# ST-LINK-SCH.net
KiCad netlist of a schematic drawn in Altium Designer
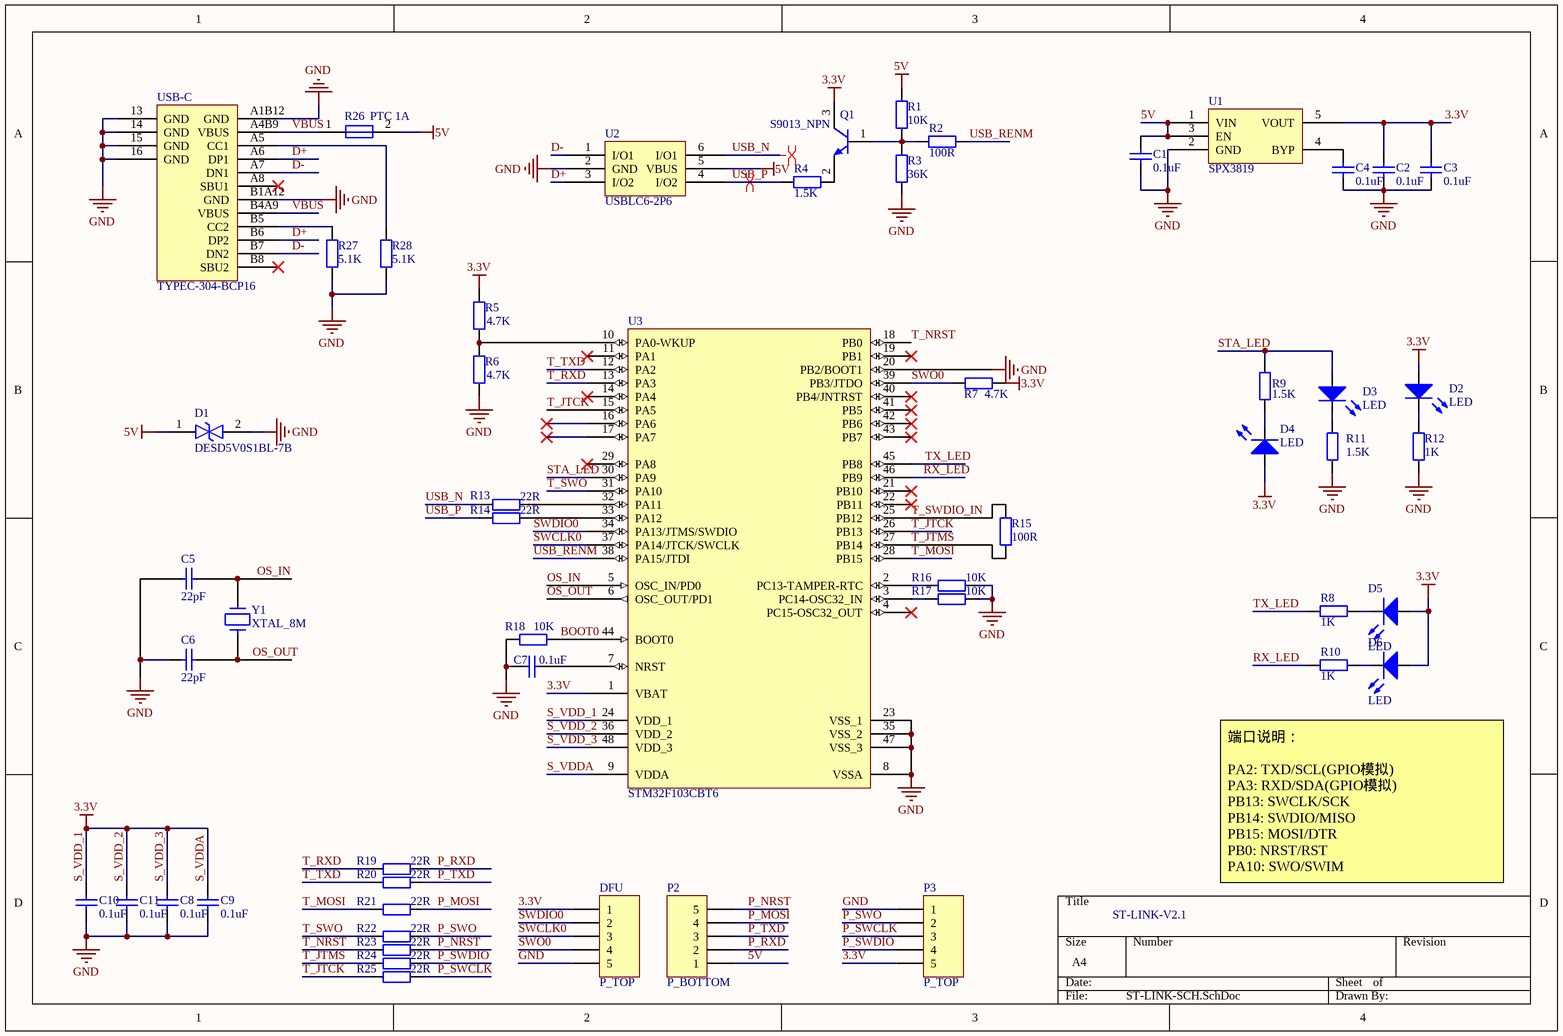
[diagram p0: ST-LINK-SCH.SchDoc]

(export (version "E")
  (design (tool "Eeschema 10.0.6"))
  (components
    (comp (ref "C1")
      (value "0.1uF")
      (footprint "0402C")
      (description "Capacitor")
      (fields (field (name "Comment") "Cap") (field (name "PUBLISHER") "Altium Limited"))
      (libsource (lib "ST-LINK-SCHLIB") (part "Cap"))
    )
    (comp (ref "C2")
      (value "0.1uF")
      (footprint "0402C")
      (description "Capacitor")
      (fields (field (name "Comment") "Cap") (field (name "PUBLISHER") "Altium Limited"))
      (libsource (lib "ST-LINK-SCHLIB") (part "Cap"))
    )
    (comp (ref "C3")
      (value "0.1uF")
      (footprint "0402C")
      (description "Capacitor")
      (fields (field (name "Comment") "Cap") (field (name "PUBLISHER") "Altium Limited"))
      (libsource (lib "ST-LINK-SCHLIB") (part "Cap"))
    )
    (comp (ref "C4")
      (value "0.1uF")
      (footprint "0402C")
      (description "Capacitor")
      (fields (field (name "Comment") "Cap") (field (name "PUBLISHER") "Altium Limited"))
      (libsource (lib "ST-LINK-SCHLIB") (part "Cap"))
    )
    (comp (ref "C5")
      (value "22pF")
      (footprint "0402C")
      (description "Capacitor")
      (fields (field (name "Comment") "Cap") (field (name "PUBLISHER") "Altium Limited"))
      (libsource (lib "ST-LINK-SCHLIB") (part "Cap"))
    )
    (comp (ref "C6")
      (value "22pF")
      (footprint "0402C")
      (description "Capacitor")
      (fields (field (name "Comment") "Cap") (field (name "PUBLISHER") "Altium Limited"))
      (libsource (lib "ST-LINK-SCHLIB") (part "Cap"))
    )
    (comp (ref "C7")
      (value "0.1uF")
      (footprint "0402C")
      (description "Capacitor")
      (fields (field (name "Comment") "Cap") (field (name "PUBLISHER") "Altium Limited"))
      (libsource (lib "ST-LINK-SCHLIB") (part "Cap"))
    )
    (comp (ref "C8")
      (value "0.1uF")
      (footprint "0402C")
      (description "Capacitor")
      (fields (field (name "Comment") "Cap") (field (name "PUBLISHER") "Altium Limited"))
      (libsource (lib "ST-LINK-SCHLIB") (part "Cap"))
    )
    (comp (ref "C9")
      (value "0.1uF")
      (footprint "0402C")
      (description "Capacitor")
      (fields (field (name "Comment") "Cap") (field (name "PUBLISHER") "Altium Limited"))
      (libsource (lib "ST-LINK-SCHLIB") (part "Cap"))
    )
    (comp (ref "C10")
      (value "0.1uF")
      (footprint "0402C")
      (description "Capacitor")
      (fields (field (name "Comment") "Cap") (field (name "PUBLISHER") "Altium Limited"))
      (libsource (lib "ST-LINK-SCHLIB") (part "Cap"))
    )
    (comp (ref "C11")
      (value "0.1uF")
      (footprint "0402C")
      (description "Capacitor")
      (fields (field (name "Comment") "Cap") (field (name "PUBLISHER") "Altium Limited"))
      (libsource (lib "ST-LINK-SCHLIB") (part "Cap"))
    )
    (comp (ref "D1")
      (value "DESD5V0S1BL-7B")
      (footprint "DESD5V0S1BL-7B")
      (description "1CHANNEL ESD")
      (libsource (lib "ST-LINK-SCHLIB") (part "DESD5V0S1BL-7B"))
    )
    (comp (ref "D2")
      (value "LED")
      (footprint "0603LED")
      (description "Typical RED, GREEN, YELLOW, AMBER GaAs LED")
      (fields (field (name "PUBLISHER") "Altium Limited"))
      (libsource (lib "ST-LINK-SCHLIB") (part "LED"))
    )
    (comp (ref "D3")
      (value "LED")
      (footprint "0603LED")
      (description "Typical RED, GREEN, YELLOW, AMBER GaAs LED")
      (fields (field (name "PUBLISHER") "Altium Limited"))
      (libsource (lib "ST-LINK-SCHLIB") (part "LED"))
    )
    (comp (ref "D4")
      (value "LED")
      (footprint "0603LED")
      (description "Typical RED, GREEN, YELLOW, AMBER GaAs LED")
      (fields (field (name "PUBLISHER") "Altium Limited"))
      (libsource (lib "ST-LINK-SCHLIB") (part "LED"))
    )
    (comp (ref "D5")
      (value "LED")
      (footprint "0603LED")
      (description "Typical RED, GREEN, YELLOW, AMBER GaAs LED")
      (fields (field (name "PUBLISHER") "Altium Limited"))
      (libsource (lib "ST-LINK-SCHLIB") (part "LED"))
    )
    (comp (ref "D6")
      (value "LED")
      (footprint "0603LED")
      (description "Typical RED, GREEN, YELLOW, AMBER GaAs LED")
      (fields (field (name "PUBLISHER") "Altium Limited"))
      (libsource (lib "ST-LINK-SCHLIB") (part "LED"))
    )
    (comp (ref "DFU")
      (value "P_TOP")
      (footprint "SIP5-1.27")
      (description "Header, 5-Pin")
      (fields (field (name "PUBLISHER") "Altium Limited"))
      (libsource (lib "ST-LINK-SCHLIB") (part "Header 5"))
    )
    (comp (ref "P2")
      (value "P_BOTTOM")
      (footprint "HEADER 5")
      (description "Header, 5-Pin")
      (fields (field (name "PUBLISHER") "Altium Limited"))
      (libsource (lib "") (part "Header 5_1"))
    )
    (comp (ref "P3")
      (value "P_TOP")
      (footprint "HEADER 5")
      (description "Header, 5-Pin")
      (fields (field (name "PUBLISHER") "Altium Limited"))
      (libsource (lib "ST-LINK-SCHLIB") (part "Header 5"))
    )
    (comp (ref "Q1")
      (value "S9013_NPN")
      (footprint "SOT-23-3")
      (fields (field (name "PUBLISHER") "Altium Limited"))
      (libsource (lib "ST-LINK-SCHLIB") (part "S9013"))
    )
    (comp (ref "R1")
      (value "10K")
      (footprint "0402R")
      (description "贴片电阻")
      (fields (field (name "Comment") "Res1") (field (name "PUBLISHER") "Altium Limited"))
      (libsource (lib "") (part "Res1_1"))
    )
    (comp (ref "R2")
      (value "100R")
      (footprint "0402R")
      (description "贴片电阻")
      (fields (field (name "Comment") "Res1") (field (name "PUBLISHER") "Altium Limited"))
      (libsource (lib "Fszhang") (part "Res1"))
    )
    (comp (ref "R3")
      (value "36K")
      (footprint "0402R")
      (description "贴片电阻")
      (fields (field (name "Comment") "Res1") (field (name "PUBLISHER") "Altium Limited"))
      (libsource (lib "") (part "Res1_1"))
    )
    (comp (ref "R4")
      (value "1.5K")
      (footprint "0402R")
      (description "贴片电阻")
      (fields (field (name "Comment") "Res1") (field (name "PUBLISHER") "Altium Limited"))
      (libsource (lib "") (part "Res1_2"))
    )
    (comp (ref "R5")
      (value "4.7K")
      (footprint "0402R")
      (description "Resistor")
      (fields (field (name "Comment") "Res2") (field (name "PUBLISHER") "Altium Limited"))
      (libsource (lib "") (part "Res2_1"))
    )
    (comp (ref "R6")
      (value "4.7K")
      (footprint "0402R")
      (description "Resistor")
      (fields (field (name "Comment") "Res2") (field (name "PUBLISHER") "Altium Limited"))
      (libsource (lib "") (part "Res2_1"))
    )
    (comp (ref "R7")
      (value "4.7K")
      (footprint "0402R")
      (description "Resistor")
      (fields (field (name "Comment") "Res2") (field (name "PUBLISHER") "Altium Limited"))
      (libsource (lib "Miscellaneous Devices") (part "Res2"))
    )
    (comp (ref "R8")
      (value "1K")
      (footprint "0402R")
      (description "Resistor")
      (fields (field (name "Comment") "Res2") (field (name "PUBLISHER") "Altium Limited"))
      (libsource (lib "Miscellaneous Devices") (part "Res2"))
    )
    (comp (ref "R9")
      (value "1.5K")
      (footprint "0402R")
      (description "Resistor")
      (fields (field (name "Comment") "Res2") (field (name "PUBLISHER") "Altium Limited"))
      (libsource (lib "") (part "Res2_1"))
    )
    (comp (ref "R10")
      (value "1K")
      (footprint "0402R")
      (description "Resistor")
      (fields (field (name "Comment") "Res2") (field (name "PUBLISHER") "Altium Limited"))
      (libsource (lib "Miscellaneous Devices") (part "Res2"))
    )
    (comp (ref "R11")
      (value "1.5K")
      (footprint "0402R")
      (description "Resistor")
      (fields (field (name "Comment") "Res2") (field (name "PUBLISHER") "Altium Limited"))
      (libsource (lib "") (part "Res2_1"))
    )
    (comp (ref "R12")
      (value "1K")
      (footprint "0402R")
      (description "Resistor")
      (fields (field (name "Comment") "Res2") (field (name "PUBLISHER") "Altium Limited"))
      (libsource (lib "") (part "Res2_1"))
    )
    (comp (ref "R13")
      (value "22R")
      (footprint "0402R")
      (description "Resistor")
      (fields (field (name "Comment") "Res2") (field (name "PUBLISHER") "Altium Limited"))
      (libsource (lib "Miscellaneous Devices") (part "Res2"))
    )
    (comp (ref "R14")
      (value "22R")
      (footprint "0402R")
      (description "Resistor")
      (fields (field (name "Comment") "Res2") (field (name "PUBLISHER") "Altium Limited"))
      (libsource (lib "Miscellaneous Devices") (part "Res2"))
    )
    (comp (ref "R15")
      (value "100R")
      (footprint "0402R")
      (description "Resistor")
      (fields (field (name "Comment") "Res2") (field (name "PUBLISHER") "Altium Limited"))
      (libsource (lib "") (part "Res2_1"))
    )
    (comp (ref "R16")
      (value "10K")
      (footprint "0402R")
      (description "贴片电阻")
      (fields (field (name "Comment") "Res1") (field (name "PUBLISHER") "Altium Limited"))
      (libsource (lib "Fszhang") (part "Res1"))
    )
    (comp (ref "R17")
      (value "10K")
      (footprint "0402R")
      (description "贴片电阻")
      (fields (field (name "Comment") "Res1") (field (name "PUBLISHER") "Altium Limited"))
      (libsource (lib "Fszhang") (part "Res1"))
    )
    (comp (ref "R18")
      (value "10K")
      (footprint "0402R")
      (description "Resistor")
      (fields (field (name "Comment") "Res2") (field (name "PUBLISHER") "Altium Limited"))
      (libsource (lib "Miscellaneous Devices") (part "Res2"))
    )
    (comp (ref "R19")
      (value "22R")
      (footprint "0402R")
      (description "Resistor")
      (fields (field (name "Comment") "Res2") (field (name "PUBLISHER") "Altium Limited"))
      (libsource (lib "Miscellaneous Devices") (part "Res2"))
    )
    (comp (ref "R20")
      (value "22R")
      (footprint "0402R")
      (description "Resistor")
      (fields (field (name "Comment") "Res2") (field (name "PUBLISHER") "Altium Limited"))
      (libsource (lib "Miscellaneous Devices") (part "Res2"))
    )
    (comp (ref "R21")
      (value "22R")
      (footprint "0402R")
      (description "Resistor")
      (fields (field (name "Comment") "Res2") (field (name "PUBLISHER") "Altium Limited"))
      (libsource (lib "Miscellaneous Devices") (part "Res2"))
    )
    (comp (ref "R22")
      (value "22R")
      (footprint "0402R")
      (description "Resistor")
      (fields (field (name "Comment") "Res2") (field (name "PUBLISHER") "Altium Limited"))
      (libsource (lib "Miscellaneous Devices") (part "Res2"))
    )
    (comp (ref "R23")
      (value "22R")
      (footprint "0402R")
      (description "Resistor")
      (fields (field (name "Comment") "Res2") (field (name "PUBLISHER") "Altium Limited"))
      (libsource (lib "Miscellaneous Devices") (part "Res2"))
    )
    (comp (ref "R24")
      (value "22R")
      (footprint "0402R")
      (description "Resistor")
      (fields (field (name "Comment") "Res2") (field (name "PUBLISHER") "Altium Limited"))
      (libsource (lib "Miscellaneous Devices") (part "Res2"))
    )
    (comp (ref "R25")
      (value "22R")
      (footprint "0402R")
      (description "Resistor")
      (fields (field (name "Comment") "Res2") (field (name "PUBLISHER") "Altium Limited"))
      (libsource (lib "Miscellaneous Devices") (part "Res2"))
    )
    (comp (ref "R26") (value "PTC 1A") (footprint "PTC_1A") (libsource (lib "ST-LINK-SCHLIB") (part "PTC保险")))
    (comp (ref "R27")
      (value "5.1K")
      (footprint "0402R")
      (description "Resistor")
      (fields (field (name "Comment") "Res2") (field (name "PUBLISHER") "Altium Limited"))
      (libsource (lib "ST-LINK-SCHLIB") (part "Res"))
    )
    (comp (ref "R28")
      (value "5.1K")
      (footprint "0402R")
      (description "Resistor")
      (fields (field (name "Comment") "Res2") (field (name "PUBLISHER") "Altium Limited"))
      (libsource (lib "ST-LINK-SCHLIB") (part "Res"))
    )
    (comp (ref "U1")
      (value "SPX3819")
      (footprint "SPX3819")
      (description "SPX3819_5VTO3V3_LDO")
      (libsource (lib "ST-LINK-SCHLIB") (part "SPX3819"))
    )
    (comp (ref "U2")
      (value "USBLC6-2P6")
      (footprint "USBLC6-2P6")
      (description "ESD PROTECTION")
      (libsource (lib "ST-LINK-SCHLIB") (part "USBLC6-2P6"))
    )
    (comp (ref "U3")
      (value "STM32F103CBT6")
      (footprint "LQFP48_L")
      (description "STM32 ARM-based 32-bit MCU with 128 Kbytes Flash, 48-pin LQFP, Industrial Temperature")
      (fields (field (name "PUBLISHER") "Altium Limited"))
      (libsource (lib "ST Microcontroller 32-Bit STM32") (part "STM32F103CBT6"))
    )
    (comp (ref "USB-C")
      (value "TYPEC-304-BCP16")
      (footprint "TYPE-C-16P")
      (description "TYPEC-16P")
      (libsource (lib "ST-LINK-SCHLIB") (part "TYPEC-304-BCP16"))
    )
    (comp (ref "Y1")
      (value "XTAL_8M")
      (footprint "SMD-5032_2P")
      (libsource (lib "ST-LINK-SCHLIB") (part "XTAL"))
    )
  )
  (nets
    (net (code "1") (name "/BOOT0") (class "Default")
      (node (ref "R18") (pin "2") (pinfunction "2_2") (pintype "passive"))
      (node (ref "U3") (pin "44") (pinfunction "BOOT0_44") (pintype "input"))
    )
    (net (code "2") (name "/D+") (class "Default")
      (node (ref "U2") (pin "3") (pinfunction "I/O2_3") (pintype "passive"))
      (node (ref "USB-C") (pin "A6") (pinfunction "DP1_A6") (pintype "passive"))
      (node (ref "USB-C") (pin "B6") (pinfunction "DP2_B6") (pintype "passive"))
    )
    (net (code "3") (name "/D-") (class "Default")
      (node (ref "U2") (pin "1") (pinfunction "I/O1_1") (pintype "passive"))
      (node (ref "USB-C") (pin "A7") (pinfunction "DN1_A7") (pintype "passive"))
      (node (ref "USB-C") (pin "B7") (pinfunction "DN2_B7") (pintype "passive"))
    )
    (net (code "4") (name "/OS_IN") (class "Default")
      (node (ref "C5") (pin "2") (pinfunction "2_2") (pintype "passive"))
      (node (ref "U3") (pin "5") (pinfunction "OSC_IN/PD0_5") (pintype "input"))
      (node (ref "Y1") (pin "2") (pinfunction "2_2") (pintype "passive"))
    )
    (net (code "5") (name "/OS_OUT") (class "Default")
      (node (ref "C6") (pin "2") (pinfunction "2_2") (pintype "passive"))
      (node (ref "U3") (pin "6") (pinfunction "OSC_OUT/PD1_6") (pintype "output"))
      (node (ref "Y1") (pin "1") (pinfunction "1_1") (pintype "passive"))
    )
    (net (code "6") (name "/P_MOSI") (class "Default")
      (node (ref "P2") (pin "4") (pinfunction "4_4") (pintype "passive"))
      (node (ref "R21") (pin "2") (pinfunction "2_2") (pintype "passive"))
    )
    (net (code "7") (name "/P_NRST") (class "Default")
      (node (ref "P2") (pin "5") (pinfunction "5_5") (pintype "passive"))
      (node (ref "R23") (pin "2") (pinfunction "2_2") (pintype "passive"))
    )
    (net (code "8") (name "/P_RXD") (class "Default")
      (node (ref "P2") (pin "2") (pinfunction "2_2") (pintype "passive"))
      (node (ref "R19") (pin "2") (pinfunction "2_2") (pintype "passive"))
    )
    (net (code "9") (name "/P_SWCLK") (class "Default")
      (node (ref "P3") (pin "3") (pinfunction "3_3") (pintype "passive"))
      (node (ref "R25") (pin "2") (pinfunction "2_2") (pintype "passive"))
    )
    (net (code "10") (name "/P_SWDIO") (class "Default")
      (node (ref "P3") (pin "4") (pinfunction "4_4") (pintype "passive"))
      (node (ref "R24") (pin "2") (pinfunction "2_2") (pintype "passive"))
    )
    (net (code "11") (name "/P_SWO") (class "Default")
      (node (ref "P3") (pin "2") (pinfunction "2_2") (pintype "passive"))
      (node (ref "R22") (pin "2") (pinfunction "2_2") (pintype "passive"))
    )
    (net (code "12") (name "/P_TXD") (class "Default")
      (node (ref "P2") (pin "3") (pinfunction "3_3") (pintype "passive"))
      (node (ref "R20") (pin "2") (pinfunction "2_2") (pintype "passive"))
    )
    (net (code "13") (name "/RX_LED") (class "Default")
      (node (ref "R10") (pin "1") (pinfunction "1_1") (pintype "passive"))
      (node (ref "U3") (pin "46") (pinfunction "PB9_46") (pintype "bidirectional"))
    )
    (net (code "14") (name "/STA_LED") (class "Default")
      (node (ref "D3") (pin "1") (pinfunction "1_1") (pintype "passive"))
      (node (ref "R9") (pin "2") (pinfunction "2_2") (pintype "passive"))
      (node (ref "U3") (pin "30") (pinfunction "PA9_30") (pintype "bidirectional"))
    )
    (net (code "15") (name "/SWCLK0") (class "Default")
      (node (ref "DFU") (pin "3") (pinfunction "3_3") (pintype "passive"))
      (node (ref "U3") (pin "37") (pinfunction "PA14/JTCK/SWCLK_37") (pintype "bidirectional"))
    )
    (net (code "16") (name "/SWDIO0") (class "Default")
      (node (ref "DFU") (pin "2") (pinfunction "2_2") (pintype "passive"))
      (node (ref "U3") (pin "34") (pinfunction "PA13/JTMS/SWDIO_34") (pintype "bidirectional"))
    )
    (net (code "17") (name "/SWO0") (class "Default")
      (node (ref "DFU") (pin "4") (pinfunction "4_4") (pintype "passive"))
      (node (ref "R7") (pin "1") (pinfunction "1_1") (pintype "passive"))
      (node (ref "U3") (pin "39") (pinfunction "PB3/JTDO_39") (pintype "bidirectional"))
    )
    (net (code "18") (name "/TX_LED") (class "Default")
      (node (ref "R8") (pin "1") (pinfunction "1_1") (pintype "passive"))
      (node (ref "U3") (pin "45") (pinfunction "PB8_45") (pintype "bidirectional"))
    )
    (net (code "19") (name "/T_JTCK") (class "Default")
      (node (ref "R25") (pin "1") (pinfunction "1_1") (pintype "passive"))
      (node (ref "U3") (pin "15") (pinfunction "PA5_15") (pintype "bidirectional"))
      (node (ref "U3") (pin "26") (pinfunction "PB13_26") (pintype "bidirectional"))
    )
    (net (code "20") (name "/T_JTMS") (class "Default")
      (node (ref "R15") (pin "1") (pinfunction "1_1") (pintype "passive"))
      (node (ref "R24") (pin "1") (pinfunction "1_1") (pintype "passive"))
      (node (ref "U3") (pin "27") (pinfunction "PB14_27") (pintype "bidirectional"))
    )
    (net (code "21") (name "/T_MOSI") (class "Default")
      (node (ref "R21") (pin "1") (pinfunction "1_1") (pintype "passive"))
      (node (ref "U3") (pin "28") (pinfunction "PB15_28") (pintype "bidirectional"))
    )
    (net (code "22") (name "/T_NRST") (class "Default")
      (node (ref "R23") (pin "1") (pinfunction "1_1") (pintype "passive"))
      (node (ref "U3") (pin "18") (pinfunction "PB0_18") (pintype "bidirectional"))
    )
    (net (code "23") (name "/T_RXD") (class "Default")
      (node (ref "R19") (pin "1") (pinfunction "1_1") (pintype "passive"))
      (node (ref "U3") (pin "13") (pinfunction "PA3_13") (pintype "bidirectional"))
    )
    (net (code "24") (name "/T_SWDIO_IN") (class "Default")
      (node (ref "R15") (pin "2") (pinfunction "2_2") (pintype "passive"))
      (node (ref "U3") (pin "25") (pinfunction "PB12_25") (pintype "bidirectional"))
    )
    (net (code "25") (name "/T_SWO") (class "Default")
      (node (ref "R22") (pin "1") (pinfunction "1_1") (pintype "passive"))
      (node (ref "U3") (pin "31") (pinfunction "PA10_31") (pintype "bidirectional"))
    )
    (net (code "26") (name "/T_TXD") (class "Default")
      (node (ref "R20") (pin "1") (pinfunction "1_1") (pintype "passive"))
      (node (ref "U3") (pin "12") (pinfunction "PA2_12") (pintype "bidirectional"))
    )
    (net (code "27") (name "/USB_N") (class "Default")
      (node (ref "R13") (pin "1") (pinfunction "1_1") (pintype "passive"))
      (node (ref "U2") (pin "6") (pinfunction "I/O1_6") (pintype "passive"))
    )
    (net (code "28") (name "/USB_P") (class "Default")
      (node (ref "R14") (pin "1") (pinfunction "1_1") (pintype "passive"))
      (node (ref "R4") (pin "2") (pinfunction "2_2") (pintype "passive"))
      (node (ref "U2") (pin "4") (pinfunction "I/O2_4") (pintype "passive"))
    )
    (net (code "29") (name "/USB_RENM") (class "Default")
      (node (ref "R2") (pin "2") (pinfunction "2_2") (pintype "passive"))
      (node (ref "U3") (pin "38") (pinfunction "PA15/JTDI_38") (pintype "bidirectional"))
    )
    (net (code "30") (name "/VBUS") (class "Default")
      (node (ref "R26") (pin "1") (pinfunction "1_1") (pintype "passive"))
      (node (ref "USB-C") (pin "A4B9") (pinfunction "VBUS_A4B9") (pintype "passive"))
      (node (ref "USB-C") (pin "B4A9") (pinfunction "VBUS_B4A9") (pintype "passive"))
    )
    (net (code "31") (name "3.3V") (class "Default")
      (node (ref "C10") (pin "2") (pinfunction "2_2") (pintype "passive"))
      (node (ref "C11") (pin "2") (pinfunction "2_2") (pintype "passive"))
      (node (ref "C2") (pin "2") (pinfunction "2_2") (pintype "passive"))
      (node (ref "C3") (pin "2") (pinfunction "2_2") (pintype "passive"))
      (node (ref "C8") (pin "2") (pinfunction "2_2") (pintype "passive"))
      (node (ref "C9") (pin "2") (pinfunction "2_2") (pintype "passive"))
      (node (ref "D2") (pin "1") (pinfunction "1_1") (pintype "passive"))
      (node (ref "D4") (pin "1") (pinfunction "1_1") (pintype "passive"))
      (node (ref "D5") (pin "1") (pinfunction "1_1") (pintype "passive"))
      (node (ref "D6") (pin "1") (pinfunction "1_1") (pintype "passive"))
      (node (ref "DFU") (pin "1") (pinfunction "1_1") (pintype "passive"))
      (node (ref "P3") (pin "5") (pinfunction "5_5") (pintype "passive"))
      (node (ref "Q1") (pin "3") (pinfunction "C_3") (pintype "passive"))
      (node (ref "R5") (pin "2") (pinfunction "2_2") (pintype "passive"))
      (node (ref "R7") (pin "2") (pinfunction "2_2") (pintype "passive"))
      (node (ref "U1") (pin "5") (pinfunction "VOUT_5") (pintype "passive"))
      (node (ref "U3") (pin "1") (pinfunction "VBAT_1") (pintype "power_in"))
      (node (ref "U3") (pin "24") (pinfunction "VDD_1_24") (pintype "power_in"))
      (node (ref "U3") (pin "36") (pinfunction "VDD_2_36") (pintype "power_in"))
      (node (ref "U3") (pin "48") (pinfunction "VDD_3_48") (pintype "power_in"))
      (node (ref "U3") (pin "9") (pinfunction "VDDA_9") (pintype "power_in"))
    )
    (net (code "32") (name "5V") (class "Default")
      (node (ref "C1") (pin "2") (pinfunction "2_2") (pintype "passive"))
      (node (ref "D1") (pin "1") (pinfunction "1_1") (pintype "passive"))
      (node (ref "P2") (pin "1") (pinfunction "1_1") (pintype "passive"))
      (node (ref "R1") (pin "1") (pinfunction "1_1") (pintype "passive"))
      (node (ref "R26") (pin "2") (pinfunction "2_2") (pintype "passive"))
      (node (ref "U1") (pin "1") (pinfunction "VIN_1") (pintype "passive"))
      (node (ref "U1") (pin "3") (pinfunction "EN_3") (pintype "passive"))
      (node (ref "U2") (pin "5") (pinfunction "VBUS_5") (pintype "passive"))
    )
    (net (code "33") (name "GND") (class "Default")
      (node (ref "C1") (pin "1") (pinfunction "1_1") (pintype "passive"))
      (node (ref "C10") (pin "1") (pinfunction "1_1") (pintype "passive"))
      (node (ref "C11") (pin "1") (pinfunction "1_1") (pintype "passive"))
      (node (ref "C2") (pin "1") (pinfunction "1_1") (pintype "passive"))
      (node (ref "C3") (pin "1") (pinfunction "1_1") (pintype "passive"))
      (node (ref "C4") (pin "1") (pinfunction "1_1") (pintype "passive"))
      (node (ref "C5") (pin "1") (pinfunction "1_1") (pintype "passive"))
      (node (ref "C6") (pin "1") (pinfunction "1_1") (pintype "passive"))
      (node (ref "C7") (pin "1") (pinfunction "1_1") (pintype "passive"))
      (node (ref "C8") (pin "1") (pinfunction "1_1") (pintype "passive"))
      (node (ref "C9") (pin "1") (pinfunction "1_1") (pintype "passive"))
      (node (ref "D1") (pin "2") (pinfunction "2_2") (pintype "passive"))
      (node (ref "DFU") (pin "5") (pinfunction "5_5") (pintype "passive"))
      (node (ref "P3") (pin "1") (pinfunction "1_1") (pintype "passive"))
      (node (ref "R11") (pin "1") (pinfunction "1_1") (pintype "passive"))
      (node (ref "R12") (pin "1") (pinfunction "1_1") (pintype "passive"))
      (node (ref "R16") (pin "2") (pinfunction "2_2") (pintype "passive"))
      (node (ref "R17") (pin "2") (pinfunction "2_2") (pintype "passive"))
      (node (ref "R18") (pin "1") (pinfunction "1_1") (pintype "passive"))
      (node (ref "R27") (pin "1") (pinfunction "1_1") (pintype "passive"))
      (node (ref "R28") (pin "1") (pinfunction "1_1") (pintype "passive"))
      (node (ref "R3") (pin "2") (pinfunction "2_2") (pintype "passive"))
      (node (ref "R6") (pin "1") (pinfunction "1_1") (pintype "passive"))
      (node (ref "U1") (pin "2") (pinfunction "GND_2") (pintype "passive"))
      (node (ref "U2") (pin "2") (pinfunction "GND_2") (pintype "passive"))
      (node (ref "U3") (pin "20") (pinfunction "PB2/BOOT1_20") (pintype "bidirectional"))
      (node (ref "U3") (pin "23") (pinfunction "VSS_1_23") (pintype "power_in"))
      (node (ref "U3") (pin "35") (pinfunction "VSS_2_35") (pintype "power_in"))
      (node (ref "U3") (pin "47") (pinfunction "VSS_3_47") (pintype "power_in"))
      (node (ref "U3") (pin "8") (pinfunction "VSSA_8") (pintype "power_in"))
      (node (ref "USB-C") (pin "13") (pinfunction "GND_13") (pintype "passive"))
      (node (ref "USB-C") (pin "14") (pinfunction "GND_14") (pintype "passive"))
      (node (ref "USB-C") (pin "15") (pinfunction "GND_15") (pintype "passive"))
      (node (ref "USB-C") (pin "16") (pinfunction "GND_16") (pintype "passive"))
      (node (ref "USB-C") (pin "A1B12") (pinfunction "GND_A1B12") (pintype "passive"))
      (node (ref "USB-C") (pin "B1A12") (pinfunction "GND_B1A12") (pintype "passive"))
    )
    (net (code "34") (name "Net-(D2-Pad2)") (class "Default")
      (node (ref "D2") (pin "2") (pinfunction "2_2") (pintype "passive"))
      (node (ref "R12") (pin "2") (pinfunction "2_2") (pintype "passive"))
    )
    (net (code "35") (name "Net-(D3-Pad2)") (class "Default")
      (node (ref "D3") (pin "2") (pinfunction "2_2") (pintype "passive"))
      (node (ref "R11") (pin "2") (pinfunction "2_2") (pintype "passive"))
    )
    (net (code "36") (name "Net-(D4-Pad2)") (class "Default")
      (node (ref "D4") (pin "2") (pinfunction "2_2") (pintype "passive"))
      (node (ref "R9") (pin "1") (pinfunction "1_1") (pintype "passive"))
    )
    (net (code "37") (name "Net-(D5-Pad2)") (class "Default")
      (node (ref "D5") (pin "2") (pinfunction "2_2") (pintype "passive"))
      (node (ref "R8") (pin "2") (pinfunction "2_2") (pintype "passive"))
    )
    (net (code "38") (name "Net-(D6-Pad2)") (class "Default")
      (node (ref "D6") (pin "2") (pinfunction "2_2") (pintype "passive"))
      (node (ref "R10") (pin "2") (pinfunction "2_2") (pintype "passive"))
    )
    (net (code "39") (name "Net-(Q1-B)") (class "Default")
      (node (ref "Q1") (pin "1") (pinfunction "B_1") (pintype "passive"))
      (node (ref "R1") (pin "2") (pinfunction "2_2") (pintype "passive"))
      (node (ref "R2") (pin "1") (pinfunction "1_1") (pintype "passive"))
      (node (ref "R3") (pin "1") (pinfunction "1_1") (pintype "passive"))
    )
    (net (code "40") (name "Net-(Q1-E)") (class "Default")
      (node (ref "Q1") (pin "2") (pinfunction "E_2") (pintype "passive"))
      (node (ref "R4") (pin "1") (pinfunction "1_1") (pintype "passive"))
    )
    (net (code "41") (name "Net-(U1-BYP)") (class "Default")
      (node (ref "C4") (pin "2") (pinfunction "2_2") (pintype "passive"))
      (node (ref "U1") (pin "4") (pinfunction "BYP_4") (pintype "passive"))
    )
    (net (code "42") (name "Net-(U3-NRST)") (class "Default")
      (node (ref "C7") (pin "2") (pinfunction "2_2") (pintype "passive"))
      (node (ref "U3") (pin "7") (pinfunction "NRST_7") (pintype "bidirectional"))
    )
    (net (code "43") (name "Net-(U3-PA0-WKUP)") (class "Default")
      (node (ref "R5") (pin "1") (pinfunction "1_1") (pintype "passive"))
      (node (ref "R6") (pin "2") (pinfunction "2_2") (pintype "passive"))
      (node (ref "U3") (pin "10") (pinfunction "PA0-WKUP_10") (pintype "bidirectional"))
    )
    (net (code "44") (name "Net-(U3-PA11)") (class "Default")
      (node (ref "R13") (pin "2") (pinfunction "2_2") (pintype "passive"))
      (node (ref "U3") (pin "32") (pinfunction "PA11_32") (pintype "bidirectional"))
    )
    (net (code "45") (name "Net-(U3-PA12)") (class "Default")
      (node (ref "R14") (pin "2") (pinfunction "2_2") (pintype "passive"))
      (node (ref "U3") (pin "33") (pinfunction "PA12_33") (pintype "bidirectional"))
    )
    (net (code "46") (name "Net-(U3-PC13-TAMPER-RTC)") (class "Default")
      (node (ref "R16") (pin "1") (pinfunction "1_1") (pintype "passive"))
      (node (ref "U3") (pin "2") (pinfunction "PC13-TAMPER-RTC_2") (pintype "bidirectional"))
    )
    (net (code "47") (name "Net-(U3-PC14-OSC32_IN)") (class "Default")
      (node (ref "R17") (pin "1") (pinfunction "1_1") (pintype "passive"))
      (node (ref "U3") (pin "3") (pinfunction "PC14-OSC32_IN_3") (pintype "bidirectional"))
    )
    (net (code "48") (name "Net-(USB-C-CC1)") (class "Default")
      (node (ref "R28") (pin "2") (pinfunction "2_2") (pintype "passive"))
      (node (ref "USB-C") (pin "A5") (pinfunction "CC1_A5") (pintype "passive"))
    )
    (net (code "49") (name "Net-(USB-C-CC2)") (class "Default")
      (node (ref "R27") (pin "2") (pinfunction "2_2") (pintype "passive"))
      (node (ref "USB-C") (pin "B5") (pinfunction "CC2_B5") (pintype "passive"))
    )
    (net (code "50") (name "unconnected-(U3-PA1-Pad11)") (class "Default")
      (node (ref "U3") (pin "11") (pinfunction "PA1_11") (pintype "bidirectional+no_connect"))
    )
    (net (code "51") (name "unconnected-(U3-PA4-Pad14)") (class "Default")
      (node (ref "U3") (pin "14") (pinfunction "PA4_14") (pintype "bidirectional+no_connect"))
    )
    (net (code "52") (name "unconnected-(U3-PA6-Pad16)") (class "Default")
      (node (ref "U3") (pin "16") (pinfunction "PA6_16") (pintype "bidirectional+no_connect"))
    )
    (net (code "53") (name "unconnected-(U3-PA7-Pad17)") (class "Default")
      (node (ref "U3") (pin "17") (pinfunction "PA7_17") (pintype "bidirectional+no_connect"))
    )
    (net (code "54") (name "unconnected-(U3-PA8-Pad29)") (class "Default")
      (node (ref "U3") (pin "29") (pinfunction "PA8_29") (pintype "bidirectional+no_connect"))
    )
    (net (code "55") (name "unconnected-(U3-PB1-Pad19)") (class "Default")
      (node (ref "U3") (pin "19") (pinfunction "PB1_19") (pintype "bidirectional+no_connect"))
    )
    (net (code "56") (name "unconnected-(U3-PB4{slash}JNTRST-Pad40)") (class "Default")
      (node (ref "U3") (pin "40") (pinfunction "PB4/JNTRST_40") (pintype "bidirectional+no_connect"))
    )
    (net (code "57") (name "unconnected-(U3-PB5-Pad41)") (class "Default")
      (node (ref "U3") (pin "41") (pinfunction "PB5_41") (pintype "bidirectional+no_connect"))
    )
    (net (code "58") (name "unconnected-(U3-PB6-Pad42)") (class "Default")
      (node (ref "U3") (pin "42") (pinfunction "PB6_42") (pintype "bidirectional+no_connect"))
    )
    (net (code "59") (name "unconnected-(U3-PB7-Pad43)") (class "Default")
      (node (ref "U3") (pin "43") (pinfunction "PB7_43") (pintype "bidirectional+no_connect"))
    )
    (net (code "60") (name "unconnected-(U3-PB10-Pad21)") (class "Default")
      (node (ref "U3") (pin "21") (pinfunction "PB10_21") (pintype "bidirectional+no_connect"))
    )
    (net (code "61") (name "unconnected-(U3-PB11-Pad22)") (class "Default")
      (node (ref "U3") (pin "22") (pinfunction "PB11_22") (pintype "bidirectional+no_connect"))
    )
    (net (code "62") (name "unconnected-(U3-PC15-OSC32_OUT-Pad4)") (class "Default")
      (node (ref "U3") (pin "4") (pinfunction "PC15-OSC32_OUT_4") (pintype "bidirectional+no_connect"))
    )
    (net (code "63") (name "unconnected-(USB-C-SBU1-PadA8)") (class "Default")
      (node (ref "USB-C") (pin "A8") (pinfunction "SBU1_A8") (pintype "passive+no_connect"))
    )
    (net (code "64") (name "unconnected-(USB-C-SBU2-PadB8)") (class "Default")
      (node (ref "USB-C") (pin "B8") (pinfunction "SBU2_B8") (pintype "passive+no_connect"))
    )
  )
)
